# ContadorAsincronico_SCH.net
KiCad netlist of a schematic drawn in Altium Designer
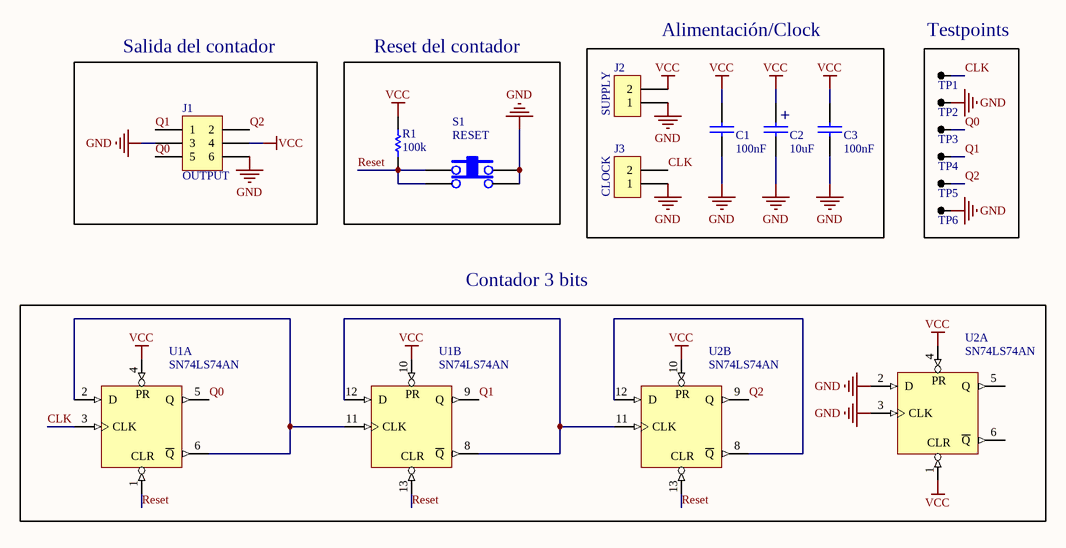
[diagram p0: ContadorAsincronico_SCH.SchDoc]

(export (version "E")
  (design (tool "Eeschema 10.0.6"))
  (components
    (comp (ref "C1") (value "100nF") (footprint "0805") (libsource (lib "LIBEBAL") (part "CAP")))
    (comp (ref "C2") (value "10uF") (footprint "CAP100RP") (libsource (lib "LIBEBAL") (part "CAPPOL")))
    (comp (ref "C3") (value "100nF") (footprint "0805") (libsource (lib "LIBEBAL") (part "CAP")))
    (comp (ref "J1") (value "OUTPUT") (footprint "SIP3*2") (libsource (lib "LIBEBAL") (part "CON3*2")))
    (comp (ref "J2") (value "SUPPLY") (footprint "BORNERA2") (libsource (lib "LIBEBAL") (part "BORNERA 2")))
    (comp (ref "J3") (value "CLOCK") (footprint "BORNERA2") (libsource (lib "LIBEBAL") (part "BORNERA 2")))
    (comp (ref "R1") (value "100k") (footprint "0805") (libsource (lib "LIBEBAL") (part "RES")))
    (comp (ref "S1")
      (value "RESET")
      (footprint "TACTSWITCH")
      (libsource (lib "LIBEBAL") (part "TACT SWITCH"))
    )
    (comp (ref "TP1") (value "CLK") (footprint "TPTH") (libsource (lib "LIBEBAL") (part "TP")))
    (comp (ref "TP2") (value "GND") (footprint "TPTH") (libsource (lib "LIBEBAL") (part "TP")))
    (comp (ref "TP3") (value "Q0") (footprint "TPTH") (libsource (lib "LIBEBAL") (part "TP")))
    (comp (ref "TP4") (value "Q1") (footprint "TPTH") (libsource (lib "LIBEBAL") (part "TP")))
    (comp (ref "TP5") (value "Q2") (footprint "TPTH") (libsource (lib "LIBEBAL") (part "TP")))
    (comp (ref "TP6") (value "GND") (footprint "TPTH") (libsource (lib "LIBEBAL") (part "TP")))
    (comp (ref "U1")
      (value "SN74LS74AN")
      (footprint "N014D")
      (description "Dual D-Type Positive-Edge-Triggered Flip-Flop with Preset and Clear")
      (libsource (lib "TI Logic Flip-Flop") (part "SN74LS74AN"))
    )
    (comp (ref "U2")
      (value "SN74LS74AN")
      (footprint "N014D")
      (description "Dual D-Type Positive-Edge-Triggered Flip-Flop with Preset and Clear")
      (libsource (lib "TI Logic Flip-Flop") (part "SN74LS74AN"))
    )
  )
  (nets
    (net (code "1") (name "/CLK") (class "Default")
      (node (ref "J3") (pin "2") (pinfunction "2_2") (pintype "passive"))
      (node (ref "TP1") (pin "1") (pinfunction "1_1") (pintype "passive"))
      (node (ref "U1") (pin "3") (pinfunction "CLK_3") (pintype "input"))
    )
    (net (code "2") (name "/Q0") (class "Default")
      (node (ref "J1") (pin "5") (pinfunction "5_5") (pintype "passive"))
      (node (ref "TP3") (pin "1") (pinfunction "1_1") (pintype "passive"))
      (node (ref "U1") (pin "5") (pinfunction "Q_5") (pintype "output"))
    )
    (net (code "3") (name "/Q1") (class "Default")
      (node (ref "J1") (pin "1") (pinfunction "1_1") (pintype "passive"))
      (node (ref "TP4") (pin "1") (pinfunction "1_1") (pintype "passive"))
      (node (ref "U1") (pin "9") (pinfunction "Q_9") (pintype "output"))
    )
    (net (code "4") (name "/Q2") (class "Default")
      (node (ref "J1") (pin "2") (pinfunction "2_2") (pintype "passive"))
      (node (ref "TP5") (pin "1") (pinfunction "1_1") (pintype "passive"))
      (node (ref "U2") (pin "9") (pinfunction "Q_9") (pintype "output"))
    )
    (net (code "5") (name "/Reset") (class "Default")
      (node (ref "R1") (pin "2") (pinfunction "2_2") (pintype "passive"))
      (node (ref "S1") (pin "1") (pinfunction "1_1") (pintype "passive"))
      (node (ref "S1") (pin "2") (pinfunction "2_2") (pintype "passive"))
      (node (ref "U1") (pin "1") (pinfunction "CLR_1") (pintype "input"))
      (node (ref "U1") (pin "13") (pinfunction "CLR_13") (pintype "input"))
      (node (ref "U2") (pin "13") (pinfunction "CLR_13") (pintype "input"))
    )
    (net (code "6") (name "GND") (class "Default")
      (node (ref "C1") (pin "2") (pinfunction "2_2") (pintype "passive"))
      (node (ref "C2") (pin "2") (pinfunction "2_2") (pintype "passive"))
      (node (ref "C3") (pin "2") (pinfunction "2_2") (pintype "passive"))
      (node (ref "J1") (pin "3") (pinfunction "3_3") (pintype "passive"))
      (node (ref "J1") (pin "6") (pinfunction "6_6") (pintype "passive"))
      (node (ref "J2") (pin "1") (pinfunction "1_1") (pintype "passive"))
      (node (ref "J3") (pin "1") (pinfunction "1_1") (pintype "passive"))
      (node (ref "S1") (pin "3") (pinfunction "3_3") (pintype "passive"))
      (node (ref "S1") (pin "4") (pinfunction "4_4") (pintype "passive"))
      (node (ref "TP2") (pin "1") (pinfunction "1_1") (pintype "passive"))
      (node (ref "TP6") (pin "1") (pinfunction "1_1") (pintype "passive"))
      (node (ref "U1") (pin "7") (pinfunction "GND_7") (pintype "power_in"))
      (node (ref "U2") (pin "2") (pinfunction "D_2") (pintype "input"))
      (node (ref "U2") (pin "3") (pinfunction "CLK_3") (pintype "input"))
      (node (ref "U2") (pin "7") (pinfunction "GND_7") (pintype "power_in"))
    )
    (net (code "7") (name "Net-(U1A-D)") (class "Default")
      (node (ref "U1") (pin "11") (pinfunction "CLK_11") (pintype "input"))
      (node (ref "U1") (pin "2") (pinfunction "D_2") (pintype "input"))
      (node (ref "U1") (pin "6") (pinfunction "~{Q}_6") (pintype "output"))
    )
    (net (code "8") (name "Net-(U1B-D)") (class "Default")
      (node (ref "U1") (pin "12") (pinfunction "D_12") (pintype "input"))
      (node (ref "U1") (pin "8") (pinfunction "~{Q}_8") (pintype "output"))
      (node (ref "U2") (pin "11") (pinfunction "CLK_11") (pintype "input"))
    )
    (net (code "9") (name "Net-(U2B-D)") (class "Default")
      (node (ref "U2") (pin "12") (pinfunction "D_12") (pintype "input"))
      (node (ref "U2") (pin "8") (pinfunction "~{Q}_8") (pintype "output"))
    )
    (net (code "10") (name "VCC") (class "Default")
      (node (ref "C1") (pin "1") (pinfunction "1_1") (pintype "passive"))
      (node (ref "C2") (pin "1") (pinfunction "1_1") (pintype "passive"))
      (node (ref "C3") (pin "1") (pinfunction "1_1") (pintype "passive"))
      (node (ref "J1") (pin "4") (pinfunction "4_4") (pintype "passive"))
      (node (ref "J2") (pin "2") (pinfunction "2_2") (pintype "passive"))
      (node (ref "R1") (pin "1") (pinfunction "1_1") (pintype "passive"))
      (node (ref "U1") (pin "10") (pinfunction "PR_10") (pintype "input"))
      (node (ref "U1") (pin "14") (pinfunction "VCC_14") (pintype "power_in"))
      (node (ref "U1") (pin "4") (pinfunction "PR_4") (pintype "input"))
      (node (ref "U2") (pin "1") (pinfunction "CLR_1") (pintype "input"))
      (node (ref "U2") (pin "10") (pinfunction "PR_10") (pintype "input"))
      (node (ref "U2") (pin "14") (pinfunction "VCC_14") (pintype "power_in"))
      (node (ref "U2") (pin "4") (pinfunction "PR_4") (pintype "input"))
    )
    (net (code "11") (name "unconnected-(U2A-Q-Pad5)") (class "Default")
      (node (ref "U2") (pin "5") (pinfunction "Q_5") (pintype "output"))
    )
    (net (code "12") (name "unconnected-(U2A-~{Q}-Pad6)") (class "Default")
      (node (ref "U2") (pin "6") (pinfunction "~{Q}_6") (pintype "output"))
    )
  )
)
